# Sheet1.net
KiCad netlist of a schematic drawn in Altium Designer
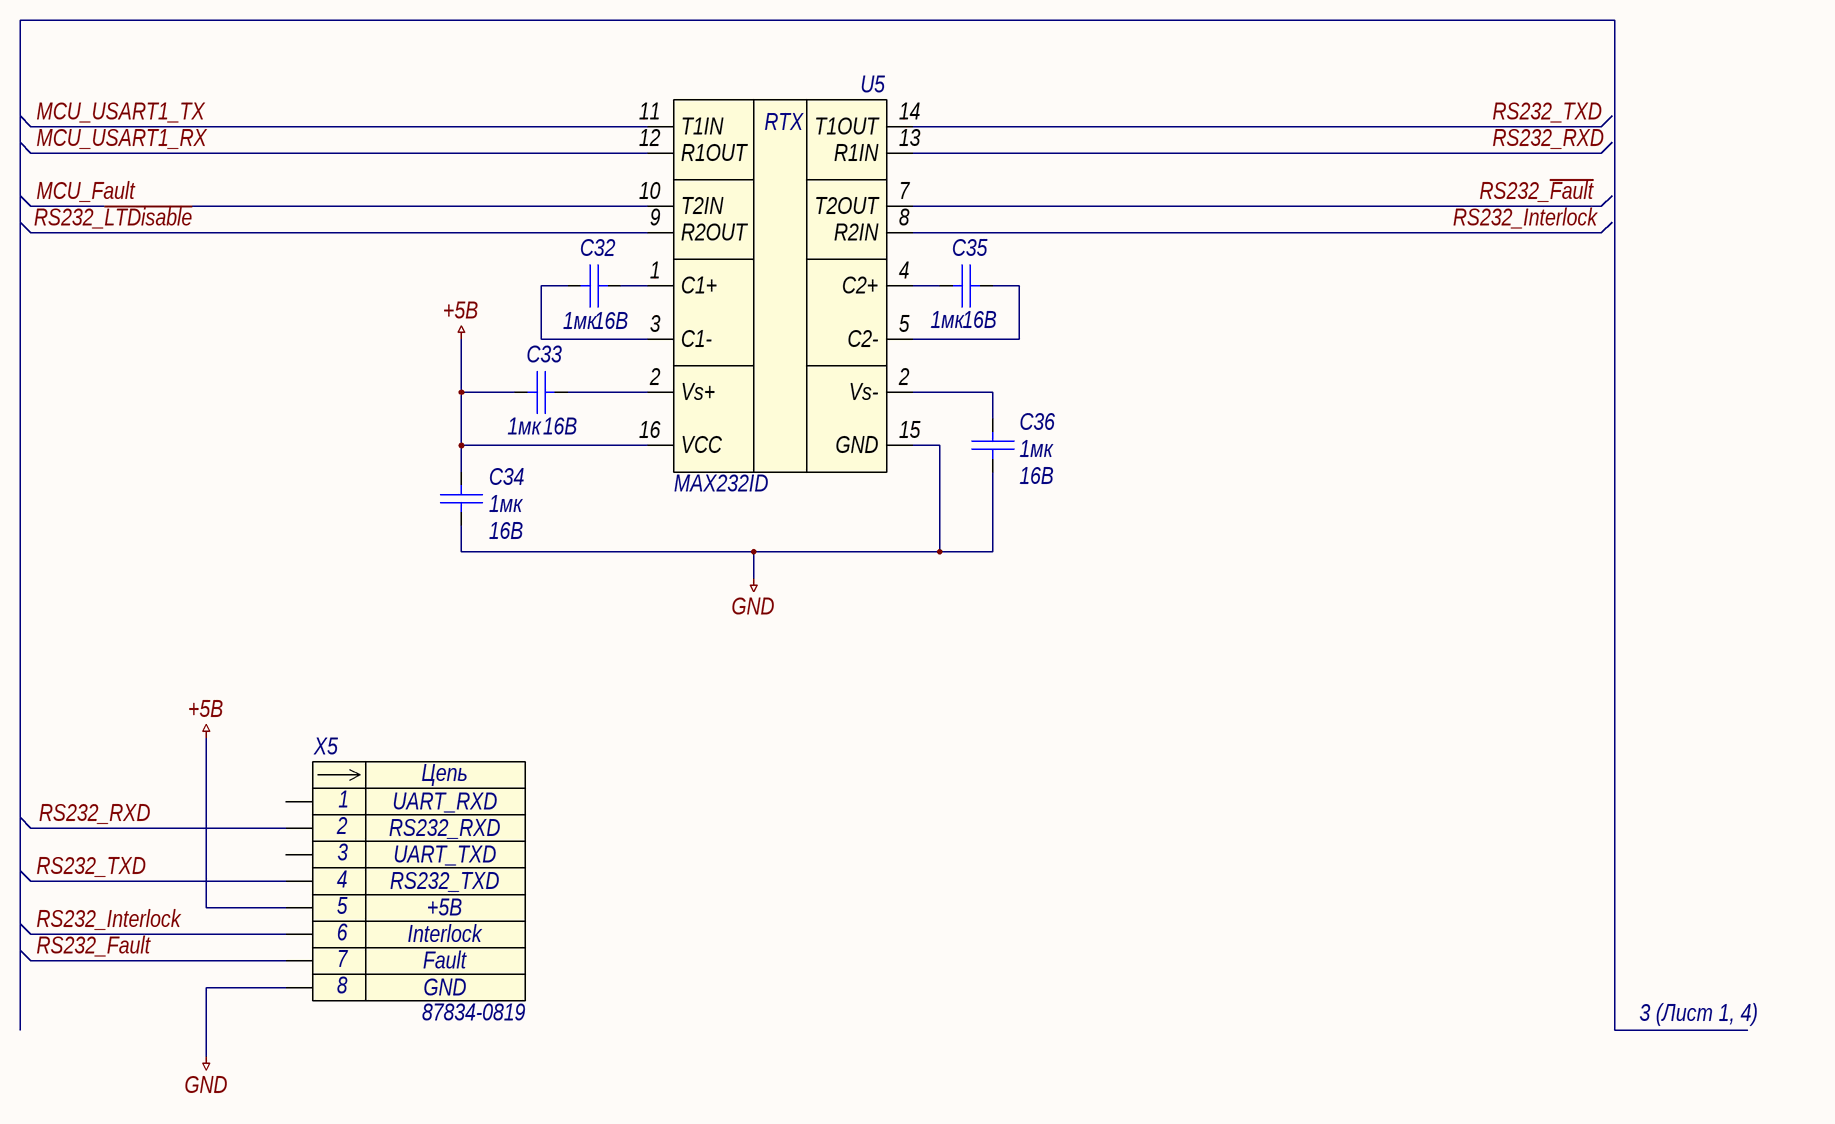
[diagram p0: Sheet1.SchDoc]

(export (version "E")
  (design (tool "Eeschema 10.0.6"))
  (components
    (comp (ref "C32")
      (value "1мк")
      (footprint "C0805_AA")
      (description "Конденсатор кер.")
      (fields (field (name "VOLTAGE") "16В"))
      (libsource (lib "Library_Diana") (part "Конденсатор кер."))
    )
    (comp (ref "C33")
      (value "1мк")
      (footprint "C0805_AA")
      (description "Конденсатор кер.")
      (fields (field (name "VOLTAGE") "16В"))
      (libsource (lib "Library_Diana") (part "Конденсатор кер."))
    )
    (comp (ref "C34")
      (value "1мк")
      (footprint "C0805_AA")
      (description "Конденсатор кер.")
      (fields (field (name "VOLTAGE") "16В"))
      (libsource (lib "Library_Diana") (part "Конденсатор кер."))
    )
    (comp (ref "C35")
      (value "1мк")
      (footprint "C0805_AA")
      (description "Конденсатор кер.")
      (fields (field (name "VOLTAGE") "16В"))
      (libsource (lib "Library_Diana") (part "Конденсатор кер."))
    )
    (comp (ref "C36")
      (value "1мк")
      (footprint "C0805_AA")
      (description "Конденсатор кер.")
      (fields (field (name "VOLTAGE") "16В"))
      (libsource (lib "Library_Diana") (part "Конденсатор кер."))
    )
    (comp (ref "U5")
      (value "MAX232ID")
      (description "Dual EIA-232 Drivers/Receivers")
      (libsource (lib "Library_Diana") (part "MAX232ID"))
    )
    (comp (ref "X5")
      (value "87834-0819")
      (description "Разъем - 8 конт. вилка")
      (fields (field (name "NAME") "87834-0819"))
      (libsource (lib "Library_Diana") (part "x8-m"))
    )
  )
  (nets
    (net (code "1") (name "+5В") (class "Default")
      (node (ref "C33") (pin "2") (pinfunction "2_2") (pintype "passive"))
      (node (ref "C34") (pin "1") (pinfunction "1_1") (pintype "passive"))
      (node (ref "U5") (pin "16") (pinfunction "VCC_16") (pintype "passive"))
      (node (ref "X5") (pin "5") (pinfunction "5_5") (pintype "passive"))
    )
    (net (code "2") (name "/MCU_Fault") (class "Default")
      (node (ref "U5") (pin "10") (pinfunction "T2IN_10") (pintype "passive"))
    )
    (net (code "3") (name "/MCU_USART1_RX") (class "Default")
      (node (ref "U5") (pin "12") (pinfunction "R1OUT_12") (pintype "passive"))
    )
    (net (code "4") (name "/MCU_USART1_TX") (class "Default")
      (node (ref "U5") (pin "11") (pinfunction "T1IN_11") (pintype "passive"))
    )
    (net (code "5") (name "/RS232_Fault") (class "Default")
      (node (ref "X5") (pin "7") (pinfunction "7_7") (pintype "passive"))
    )
    (net (code "6") (name "/RS232_Interlock") (class "Default")
      (node (ref "U5") (pin "8") (pinfunction "R2IN_8") (pintype "passive"))
      (node (ref "X5") (pin "6") (pinfunction "6_6") (pintype "passive"))
    )
    (net (code "7") (name "/RS232_RXD") (class "Default")
      (node (ref "U5") (pin "13") (pinfunction "R1IN_13") (pintype "passive"))
      (node (ref "X5") (pin "2") (pinfunction "2_2") (pintype "passive"))
    )
    (net (code "8") (name "/RS232_TXD") (class "Default")
      (node (ref "U5") (pin "14") (pinfunction "T1OUT_14") (pintype "passive"))
      (node (ref "X5") (pin "4") (pinfunction "4_4") (pintype "passive"))
    )
    (net (code "9") (name "/RS232_~{Fault}") (class "Default")
      (node (ref "U5") (pin "7") (pinfunction "T2OUT_7") (pintype "passive"))
    )
    (net (code "10") (name "/RS232_~{LTDisable}") (class "Default")
      (node (ref "U5") (pin "9") (pinfunction "R2OUT_9") (pintype "passive"))
    )
    (net (code "11") (name "GND") (class "Default")
      (node (ref "C34") (pin "2") (pinfunction "2_2") (pintype "passive"))
      (node (ref "C36") (pin "2") (pinfunction "2_2") (pintype "passive"))
      (node (ref "U5") (pin "15") (pinfunction "GND_15") (pintype "passive"))
      (node (ref "X5") (pin "8") (pinfunction "8_8") (pintype "passive"))
    )
    (net (code "12") (name "Net-(U5-C1+)") (class "Default")
      (node (ref "C32") (pin "1") (pinfunction "1_1") (pintype "passive"))
      (node (ref "U5") (pin "1") (pinfunction "C1+_1") (pintype "passive"))
    )
    (net (code "13") (name "Net-(U5-C1-)") (class "Default")
      (node (ref "C32") (pin "2") (pinfunction "2_2") (pintype "passive"))
      (node (ref "U5") (pin "3") (pinfunction "C1-_3") (pintype "passive"))
    )
    (net (code "14") (name "Net-(U5-C2+)") (class "Default")
      (node (ref "C35") (pin "2") (pinfunction "2_2") (pintype "passive"))
      (node (ref "U5") (pin "4") (pinfunction "C2+_4") (pintype "passive"))
    )
    (net (code "15") (name "Net-(U5-C2-)") (class "Default")
      (node (ref "C35") (pin "1") (pinfunction "1_1") (pintype "passive"))
      (node (ref "U5") (pin "5") (pinfunction "C2-_5") (pintype "passive"))
    )
    (net (code "16") (name "Net-(U5-Vs+)") (class "Default")
      (node (ref "C33") (pin "1") (pinfunction "1_1") (pintype "passive"))
      (node (ref "U5") (pin "2") (pinfunction "Vs+_2") (pintype "passive"))
    )
    (net (code "17") (name "Net-(U5-Vs-)") (class "Default")
      (node (ref "C36") (pin "1") (pinfunction "1_1") (pintype "passive"))
      (node (ref "U5") (pin "2") (pinfunction "Vs-_2") (pintype "passive"))
    )
    (net (code "18") (name "unconnected-(X5-Pad1)") (class "Default")
      (node (ref "X5") (pin "1") (pinfunction "1_1") (pintype "passive"))
    )
    (net (code "19") (name "unconnected-(X5-Pad3)") (class "Default")
      (node (ref "X5") (pin "3") (pinfunction "3_3") (pintype "passive"))
    )
  )
)
